# SchematicMasterModulePCB.net
KiCad netlist of a schematic drawn in EAGLE
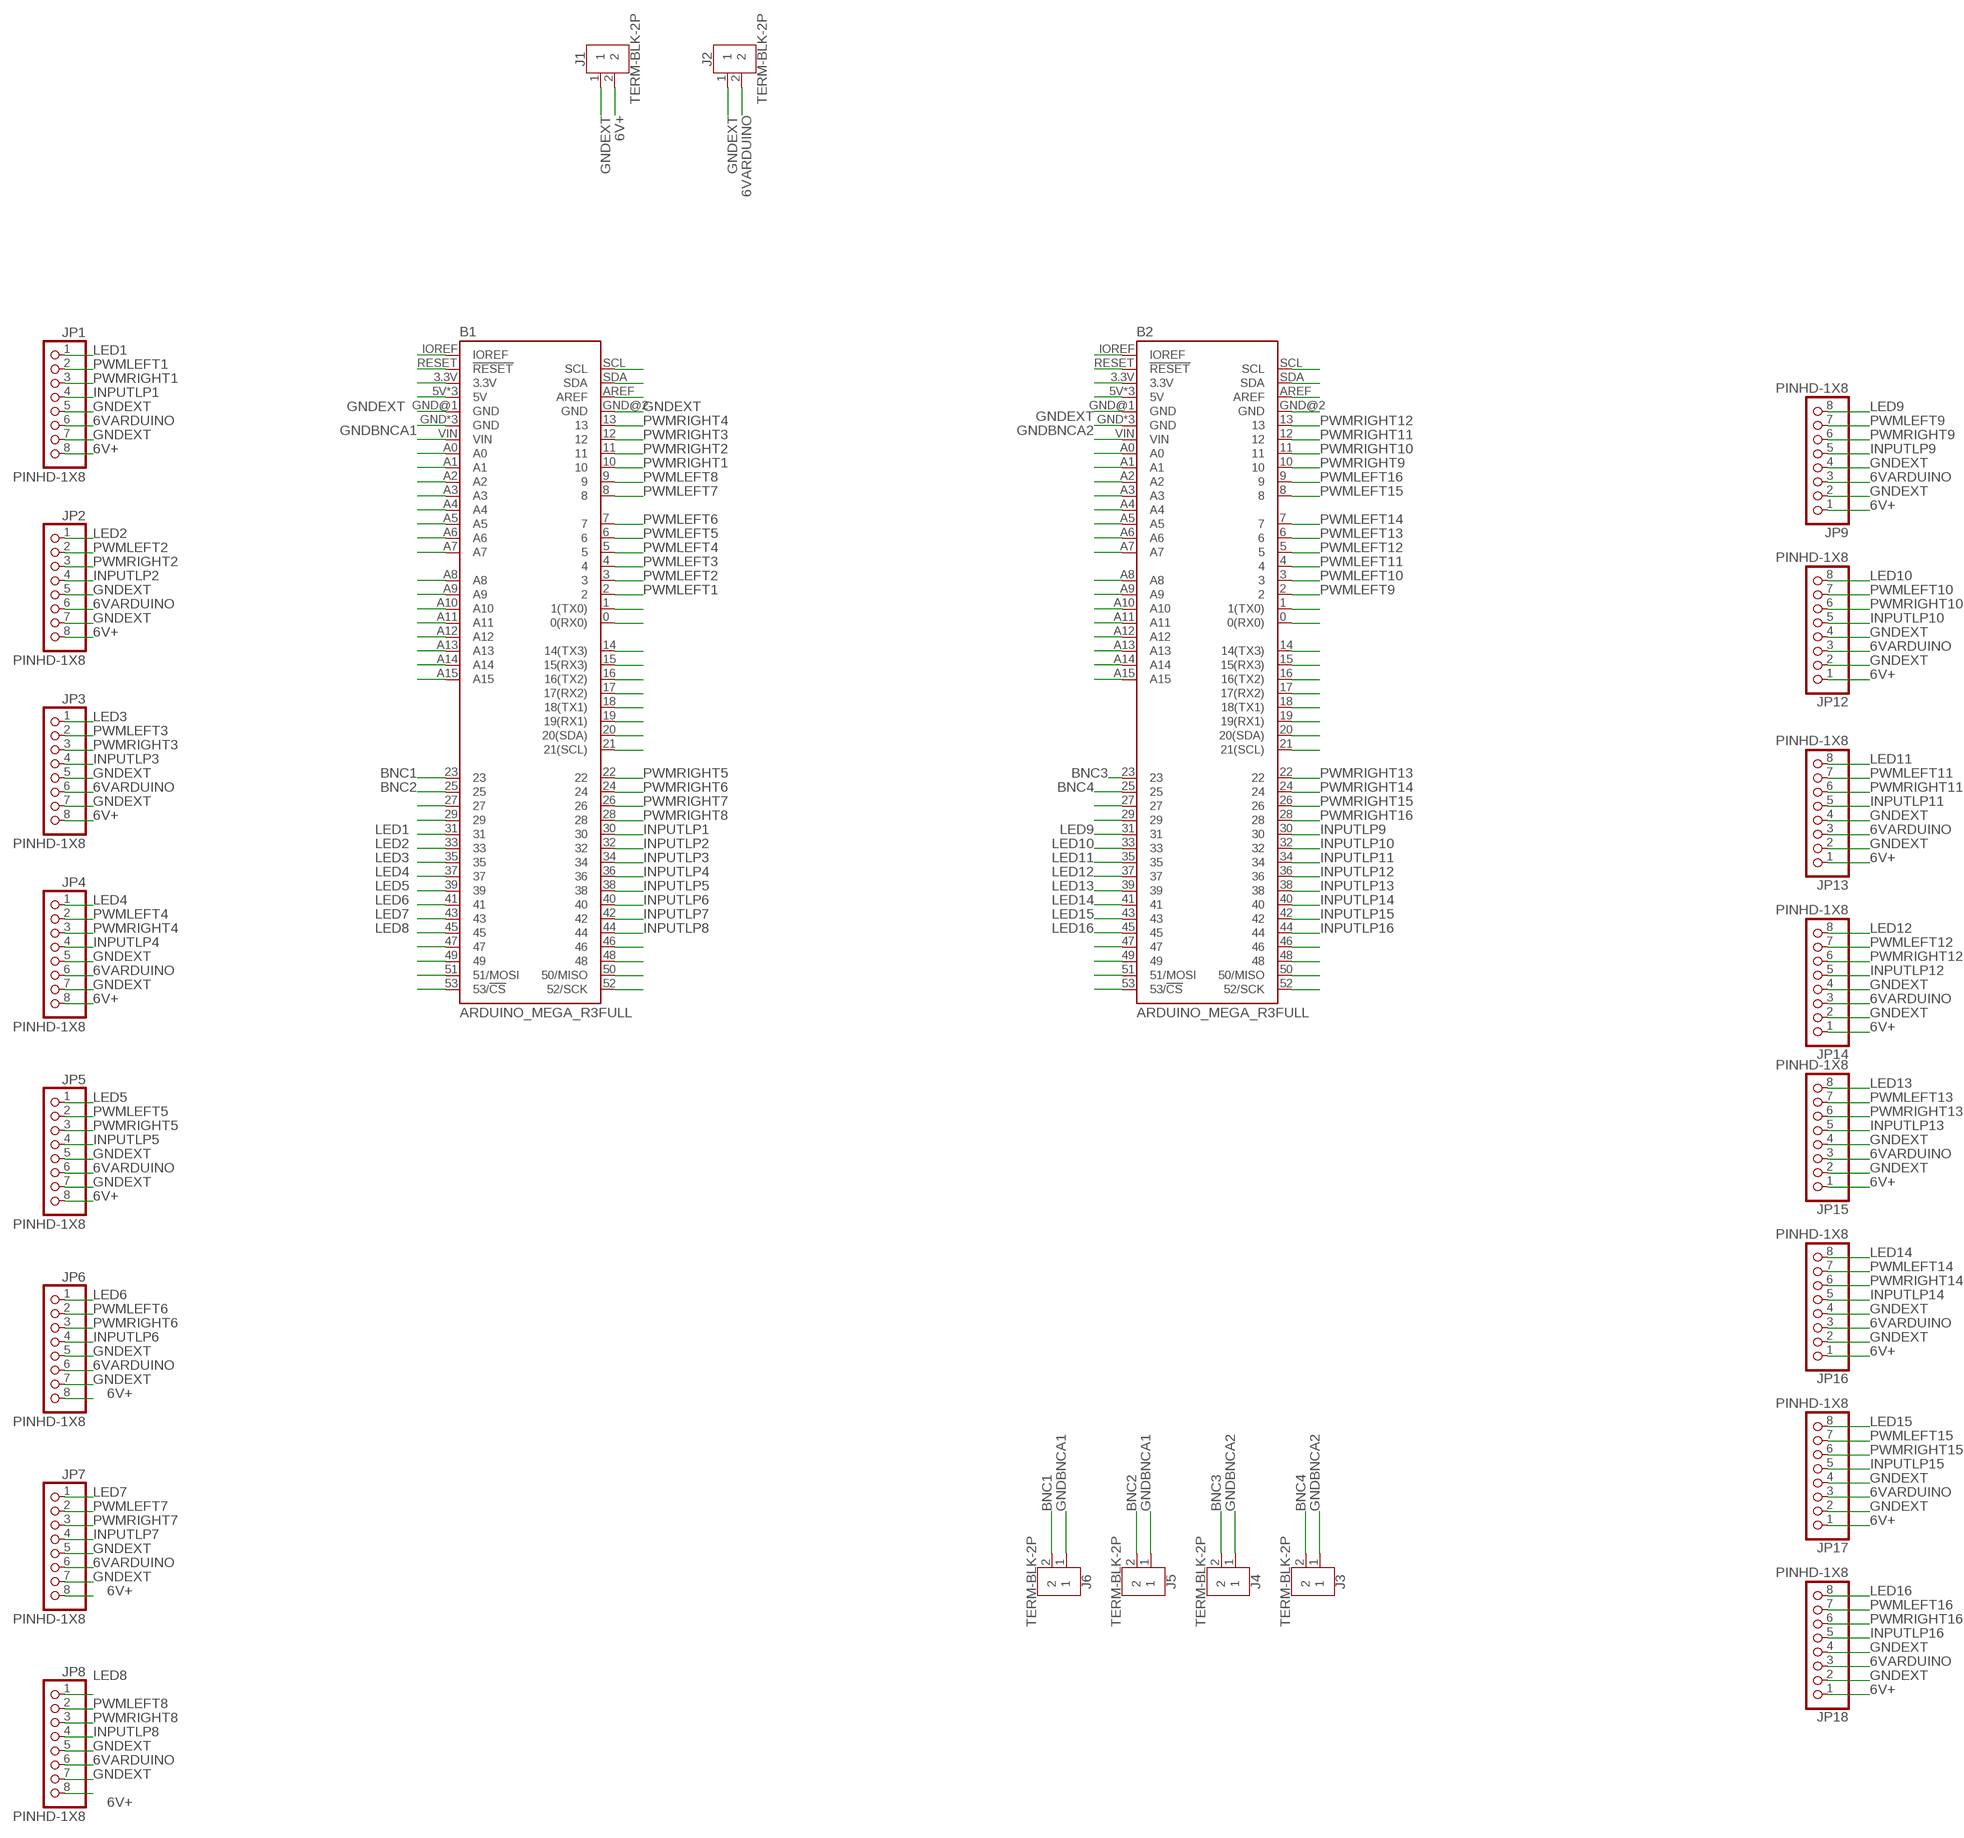
[diagram p0: schematic, sheet 1]

(export (version "E")
  (design (tool "Eeschema 10.0.6"))
  (components
    (comp (ref "B1")
      (value "ARDUINO_MEGA_R3FULL")
      (footprint "eagle-import:ARDUINO_MEGA_NO_SILK")
      (libsource (lib "eagle-import") (part "ARDUINO_MEGA_R3FULL"))
    )
    (comp (ref "B2")
      (value "ARDUINO_MEGA_R3FULL")
      (footprint "eagle-import:ARDUINO_MEGA_NO_SILK")
      (libsource (lib "eagle-import") (part "ARDUINO_MEGA_R3FULL"))
    )
    (comp (ref "J1")
      (value "TERM-BLK-2P")
      (footprint "eagle-import:TERMBLK_508-2N")
      (fields (field (name "MANUFACTURER") "TE Connectivity AMP Connectors") (field (name "MPN") "282837-2"))
      (libsource (lib "eagle-import") (part "2PINSCREWTERMINAL282837-2"))
    )
    (comp (ref "J2")
      (value "TERM-BLK-2P")
      (footprint "eagle-import:TERMBLK_508-2N")
      (fields (field (name "MANUFACTURER") "TE Connectivity AMP Connectors") (field (name "MPN") "282837-2"))
      (libsource (lib "eagle-import") (part "2PINSCREWTERMINAL282837-2"))
    )
    (comp (ref "J3")
      (value "TERM-BLK-2P")
      (footprint "eagle-import:TERMBLK_508-2N")
      (fields (field (name "MANUFACTURER") "TE Connectivity AMP Connectors") (field (name "MPN") "282837-2"))
      (libsource (lib "eagle-import") (part "2PINSCREWTERMINAL282837-2"))
    )
    (comp (ref "J4")
      (value "TERM-BLK-2P")
      (footprint "eagle-import:TERMBLK_508-2N")
      (fields (field (name "MANUFACTURER") "TE Connectivity AMP Connectors") (field (name "MPN") "282837-2"))
      (libsource (lib "eagle-import") (part "2PINSCREWTERMINAL282837-2"))
    )
    (comp (ref "J5")
      (value "TERM-BLK-2P")
      (footprint "eagle-import:TERMBLK_508-2N")
      (fields (field (name "MANUFACTURER") "TE Connectivity AMP Connectors") (field (name "MPN") "282837-2"))
      (libsource (lib "eagle-import") (part "2PINSCREWTERMINAL282837-2"))
    )
    (comp (ref "J6")
      (value "TERM-BLK-2P")
      (footprint "eagle-import:TERMBLK_508-2N")
      (fields (field (name "MANUFACTURER") "TE Connectivity AMP Connectors") (field (name "MPN") "282837-2"))
      (libsource (lib "eagle-import") (part "2PINSCREWTERMINAL282837-2"))
    )
    (comp (ref "JP1")
      (value "PINHD-1X8")
      (footprint "eagle-import:1X08")
      (fields (field (name "MANUFACTURER") "Generic"))
      (libsource (lib "eagle-import") (part "PINHD-1X8"))
    )
    (comp (ref "JP2")
      (value "PINHD-1X8")
      (footprint "eagle-import:1X08")
      (fields (field (name "MANUFACTURER") "Generic"))
      (libsource (lib "eagle-import") (part "PINHD-1X8"))
    )
    (comp (ref "JP3")
      (value "PINHD-1X8")
      (footprint "eagle-import:1X08")
      (fields (field (name "MANUFACTURER") "Generic"))
      (libsource (lib "eagle-import") (part "PINHD-1X8"))
    )
    (comp (ref "JP4")
      (value "PINHD-1X8")
      (footprint "eagle-import:1X08")
      (fields (field (name "MANUFACTURER") "Generic"))
      (libsource (lib "eagle-import") (part "PINHD-1X8"))
    )
    (comp (ref "JP5")
      (value "PINHD-1X8")
      (footprint "eagle-import:1X08")
      (fields (field (name "MANUFACTURER") "Generic"))
      (libsource (lib "eagle-import") (part "PINHD-1X8"))
    )
    (comp (ref "JP6")
      (value "PINHD-1X8")
      (footprint "eagle-import:1X08")
      (fields (field (name "MANUFACTURER") "Generic"))
      (libsource (lib "eagle-import") (part "PINHD-1X8"))
    )
    (comp (ref "JP7")
      (value "PINHD-1X8")
      (footprint "eagle-import:1X08")
      (fields (field (name "MANUFACTURER") "Generic"))
      (libsource (lib "eagle-import") (part "PINHD-1X8"))
    )
    (comp (ref "JP8")
      (value "PINHD-1X8")
      (footprint "eagle-import:1X08")
      (fields (field (name "MANUFACTURER") "Generic"))
      (libsource (lib "eagle-import") (part "PINHD-1X8"))
    )
    (comp (ref "JP9")
      (value "PINHD-1X8")
      (footprint "eagle-import:1X08")
      (fields (field (name "MANUFACTURER") "Generic"))
      (libsource (lib "eagle-import") (part "PINHD-1X8"))
    )
    (comp (ref "JP12")
      (value "PINHD-1X8")
      (footprint "eagle-import:1X08")
      (fields (field (name "MANUFACTURER") "Generic"))
      (libsource (lib "eagle-import") (part "PINHD-1X8"))
    )
    (comp (ref "JP13")
      (value "PINHD-1X8")
      (footprint "eagle-import:1X08")
      (fields (field (name "MANUFACTURER") "Generic"))
      (libsource (lib "eagle-import") (part "PINHD-1X8"))
    )
    (comp (ref "JP14")
      (value "PINHD-1X8")
      (footprint "eagle-import:1X08")
      (fields (field (name "MANUFACTURER") "Generic"))
      (libsource (lib "eagle-import") (part "PINHD-1X8"))
    )
    (comp (ref "JP15")
      (value "PINHD-1X8")
      (footprint "eagle-import:1X08")
      (fields (field (name "MANUFACTURER") "Generic"))
      (libsource (lib "eagle-import") (part "PINHD-1X8"))
    )
    (comp (ref "JP16")
      (value "PINHD-1X8")
      (footprint "eagle-import:1X08")
      (fields (field (name "MANUFACTURER") "Generic"))
      (libsource (lib "eagle-import") (part "PINHD-1X8"))
    )
    (comp (ref "JP17")
      (value "PINHD-1X8")
      (footprint "eagle-import:1X08")
      (fields (field (name "MANUFACTURER") "Generic"))
      (libsource (lib "eagle-import") (part "PINHD-1X8"))
    )
    (comp (ref "JP18")
      (value "PINHD-1X8")
      (footprint "eagle-import:1X08")
      (fields (field (name "MANUFACTURER") "Generic"))
      (libsource (lib "eagle-import") (part "PINHD-1X8"))
    )
  )
  (nets
    (net (code "1") (name "/6V+") (class "Default")
      (node (ref "J1") (pin "2") (pinfunction "2_2") (pintype "bidirectional"))
      (node (ref "JP1") (pin "8") (pinfunction "8_8") (pintype "passive"))
      (node (ref "JP12") (pin "1") (pinfunction "1_1") (pintype "passive"))
      (node (ref "JP13") (pin "1") (pinfunction "1_1") (pintype "passive"))
      (node (ref "JP14") (pin "1") (pinfunction "1_1") (pintype "passive"))
      (node (ref "JP15") (pin "1") (pinfunction "1_1") (pintype "passive"))
      (node (ref "JP16") (pin "1") (pinfunction "1_1") (pintype "passive"))
      (node (ref "JP17") (pin "1") (pinfunction "1_1") (pintype "passive"))
      (node (ref "JP18") (pin "1") (pinfunction "1_1") (pintype "passive"))
      (node (ref "JP2") (pin "8") (pinfunction "8_8") (pintype "passive"))
      (node (ref "JP3") (pin "8") (pinfunction "8_8") (pintype "passive"))
      (node (ref "JP4") (pin "8") (pinfunction "8_8") (pintype "passive"))
      (node (ref "JP5") (pin "8") (pinfunction "8_8") (pintype "passive"))
      (node (ref "JP6") (pin "8") (pinfunction "8_8") (pintype "passive"))
      (node (ref "JP7") (pin "8") (pinfunction "8_8") (pintype "passive"))
      (node (ref "JP8") (pin "8") (pinfunction "8_8") (pintype "passive"))
      (node (ref "JP9") (pin "1") (pinfunction "1_1") (pintype "passive"))
    )
    (net (code "2") (name "/6VARDUINO") (class "Default")
      (node (ref "J2") (pin "2") (pinfunction "2_2") (pintype "bidirectional"))
      (node (ref "JP1") (pin "6") (pinfunction "6_6") (pintype "passive"))
      (node (ref "JP12") (pin "3") (pinfunction "3_3") (pintype "passive"))
      (node (ref "JP13") (pin "3") (pinfunction "3_3") (pintype "passive"))
      (node (ref "JP14") (pin "3") (pinfunction "3_3") (pintype "passive"))
      (node (ref "JP15") (pin "3") (pinfunction "3_3") (pintype "passive"))
      (node (ref "JP16") (pin "3") (pinfunction "3_3") (pintype "passive"))
      (node (ref "JP17") (pin "3") (pinfunction "3_3") (pintype "passive"))
      (node (ref "JP18") (pin "3") (pinfunction "3_3") (pintype "passive"))
      (node (ref "JP2") (pin "6") (pinfunction "6_6") (pintype "passive"))
      (node (ref "JP3") (pin "6") (pinfunction "6_6") (pintype "passive"))
      (node (ref "JP4") (pin "6") (pinfunction "6_6") (pintype "passive"))
      (node (ref "JP5") (pin "6") (pinfunction "6_6") (pintype "passive"))
      (node (ref "JP6") (pin "6") (pinfunction "6_6") (pintype "passive"))
      (node (ref "JP7") (pin "6") (pinfunction "6_6") (pintype "passive"))
      (node (ref "JP8") (pin "6") (pinfunction "6_6") (pintype "passive"))
      (node (ref "JP9") (pin "3") (pinfunction "3_3") (pintype "passive"))
    )
    (net (code "3") (name "/BNC1") (class "Default")
      (node (ref "B1") (pin "23") (pinfunction "23_23") (pintype "bidirectional"))
      (node (ref "J6") (pin "2") (pinfunction "2_2") (pintype "bidirectional"))
    )
    (net (code "4") (name "/BNC2") (class "Default")
      (node (ref "B1") (pin "25") (pinfunction "25_25") (pintype "bidirectional"))
      (node (ref "J5") (pin "2") (pinfunction "2_2") (pintype "bidirectional"))
    )
    (net (code "5") (name "/BNC3") (class "Default")
      (node (ref "B2") (pin "23") (pinfunction "23_23") (pintype "bidirectional"))
      (node (ref "J4") (pin "2") (pinfunction "2_2") (pintype "bidirectional"))
    )
    (net (code "6") (name "/BNC4") (class "Default")
      (node (ref "B2") (pin "25") (pinfunction "25_25") (pintype "bidirectional"))
      (node (ref "J3") (pin "2") (pinfunction "2_2") (pintype "bidirectional"))
    )
    (net (code "7") (name "/GNDBNCA1") (class "Default")
      (node (ref "B1") (pin "GND") (pinfunction "GND_GND") (pintype "bidirectional"))
      (node (ref "B1") (pin "GND@3") (pinfunction "GND_GND@3") (pintype "bidirectional"))
      (node (ref "B1") (pin "GND@4") (pinfunction "GND_GND@4") (pintype "bidirectional"))
      (node (ref "J5") (pin "1") (pinfunction "1_1") (pintype "bidirectional"))
      (node (ref "J6") (pin "1") (pinfunction "1_1") (pintype "bidirectional"))
    )
    (net (code "8") (name "/GNDBNCA2") (class "Default")
      (node (ref "B2") (pin "GND") (pinfunction "GND_GND") (pintype "bidirectional"))
      (node (ref "B2") (pin "GND@3") (pinfunction "GND_GND@3") (pintype "bidirectional"))
      (node (ref "B2") (pin "GND@4") (pinfunction "GND_GND@4") (pintype "bidirectional"))
      (node (ref "J3") (pin "1") (pinfunction "1_1") (pintype "bidirectional"))
      (node (ref "J4") (pin "1") (pinfunction "1_1") (pintype "bidirectional"))
    )
    (net (code "9") (name "/GNDEXT") (class "Default")
      (node (ref "B1") (pin "GND@1") (pinfunction "GND_GND@1") (pintype "bidirectional"))
      (node (ref "B1") (pin "GND@2") (pinfunction "GND_GND@2") (pintype "bidirectional"))
      (node (ref "B2") (pin "GND@1") (pinfunction "GND_GND@1") (pintype "bidirectional"))
      (node (ref "J1") (pin "1") (pinfunction "1_1") (pintype "bidirectional"))
      (node (ref "J2") (pin "1") (pinfunction "1_1") (pintype "bidirectional"))
      (node (ref "JP1") (pin "5") (pinfunction "5_5") (pintype "passive"))
      (node (ref "JP1") (pin "7") (pinfunction "7_7") (pintype "passive"))
      (node (ref "JP12") (pin "2") (pinfunction "2_2") (pintype "passive"))
      (node (ref "JP12") (pin "4") (pinfunction "4_4") (pintype "passive"))
      (node (ref "JP13") (pin "2") (pinfunction "2_2") (pintype "passive"))
      (node (ref "JP13") (pin "4") (pinfunction "4_4") (pintype "passive"))
      (node (ref "JP14") (pin "2") (pinfunction "2_2") (pintype "passive"))
      (node (ref "JP14") (pin "4") (pinfunction "4_4") (pintype "passive"))
      (node (ref "JP15") (pin "2") (pinfunction "2_2") (pintype "passive"))
      (node (ref "JP15") (pin "4") (pinfunction "4_4") (pintype "passive"))
      (node (ref "JP16") (pin "2") (pinfunction "2_2") (pintype "passive"))
      (node (ref "JP16") (pin "4") (pinfunction "4_4") (pintype "passive"))
      (node (ref "JP17") (pin "2") (pinfunction "2_2") (pintype "passive"))
      (node (ref "JP17") (pin "4") (pinfunction "4_4") (pintype "passive"))
      (node (ref "JP18") (pin "2") (pinfunction "2_2") (pintype "passive"))
      (node (ref "JP18") (pin "4") (pinfunction "4_4") (pintype "passive"))
      (node (ref "JP2") (pin "5") (pinfunction "5_5") (pintype "passive"))
      (node (ref "JP2") (pin "7") (pinfunction "7_7") (pintype "passive"))
      (node (ref "JP3") (pin "5") (pinfunction "5_5") (pintype "passive"))
      (node (ref "JP3") (pin "7") (pinfunction "7_7") (pintype "passive"))
      (node (ref "JP4") (pin "5") (pinfunction "5_5") (pintype "passive"))
      (node (ref "JP4") (pin "7") (pinfunction "7_7") (pintype "passive"))
      (node (ref "JP5") (pin "5") (pinfunction "5_5") (pintype "passive"))
      (node (ref "JP5") (pin "7") (pinfunction "7_7") (pintype "passive"))
      (node (ref "JP6") (pin "5") (pinfunction "5_5") (pintype "passive"))
      (node (ref "JP6") (pin "7") (pinfunction "7_7") (pintype "passive"))
      (node (ref "JP7") (pin "5") (pinfunction "5_5") (pintype "passive"))
      (node (ref "JP7") (pin "7") (pinfunction "7_7") (pintype "passive"))
      (node (ref "JP8") (pin "5") (pinfunction "5_5") (pintype "passive"))
      (node (ref "JP8") (pin "7") (pinfunction "7_7") (pintype "passive"))
      (node (ref "JP9") (pin "2") (pinfunction "2_2") (pintype "passive"))
      (node (ref "JP9") (pin "4") (pinfunction "4_4") (pintype "passive"))
    )
    (net (code "10") (name "/INPUTLP1") (class "Default")
      (node (ref "B1") (pin "30") (pinfunction "30_30") (pintype "bidirectional"))
      (node (ref "JP1") (pin "4") (pinfunction "4_4") (pintype "passive"))
    )
    (net (code "11") (name "/INPUTLP2") (class "Default")
      (node (ref "B1") (pin "32") (pinfunction "32_32") (pintype "bidirectional"))
      (node (ref "JP2") (pin "4") (pinfunction "4_4") (pintype "passive"))
    )
    (net (code "12") (name "/INPUTLP3") (class "Default")
      (node (ref "B1") (pin "34") (pinfunction "34_34") (pintype "bidirectional"))
      (node (ref "JP3") (pin "4") (pinfunction "4_4") (pintype "passive"))
    )
    (net (code "13") (name "/INPUTLP4") (class "Default")
      (node (ref "B1") (pin "36") (pinfunction "36_36") (pintype "bidirectional"))
      (node (ref "JP4") (pin "4") (pinfunction "4_4") (pintype "passive"))
    )
    (net (code "14") (name "/INPUTLP5") (class "Default")
      (node (ref "B1") (pin "38") (pinfunction "38_38") (pintype "bidirectional"))
      (node (ref "JP5") (pin "4") (pinfunction "4_4") (pintype "passive"))
    )
    (net (code "15") (name "/INPUTLP6") (class "Default")
      (node (ref "B1") (pin "40") (pinfunction "40_40") (pintype "bidirectional"))
      (node (ref "JP6") (pin "4") (pinfunction "4_4") (pintype "passive"))
    )
    (net (code "16") (name "/INPUTLP7") (class "Default")
      (node (ref "B1") (pin "42") (pinfunction "42_42") (pintype "bidirectional"))
      (node (ref "JP7") (pin "4") (pinfunction "4_4") (pintype "passive"))
    )
    (net (code "17") (name "/INPUTLP8") (class "Default")
      (node (ref "B1") (pin "44") (pinfunction "44_44") (pintype "bidirectional"))
      (node (ref "JP8") (pin "4") (pinfunction "4_4") (pintype "passive"))
    )
    (net (code "18") (name "/INPUTLP9") (class "Default")
      (node (ref "B2") (pin "30") (pinfunction "30_30") (pintype "bidirectional"))
      (node (ref "JP9") (pin "5") (pinfunction "5_5") (pintype "passive"))
    )
    (net (code "19") (name "/INPUTLP10") (class "Default")
      (node (ref "B2") (pin "32") (pinfunction "32_32") (pintype "bidirectional"))
      (node (ref "JP12") (pin "5") (pinfunction "5_5") (pintype "passive"))
    )
    (net (code "20") (name "/INPUTLP11") (class "Default")
      (node (ref "B2") (pin "34") (pinfunction "34_34") (pintype "bidirectional"))
      (node (ref "JP13") (pin "5") (pinfunction "5_5") (pintype "passive"))
    )
    (net (code "21") (name "/INPUTLP12") (class "Default")
      (node (ref "B2") (pin "36") (pinfunction "36_36") (pintype "bidirectional"))
      (node (ref "JP14") (pin "5") (pinfunction "5_5") (pintype "passive"))
    )
    (net (code "22") (name "/INPUTLP13") (class "Default")
      (node (ref "B2") (pin "38") (pinfunction "38_38") (pintype "bidirectional"))
      (node (ref "JP15") (pin "5") (pinfunction "5_5") (pintype "passive"))
    )
    (net (code "23") (name "/INPUTLP14") (class "Default")
      (node (ref "B2") (pin "40") (pinfunction "40_40") (pintype "bidirectional"))
      (node (ref "JP16") (pin "5") (pinfunction "5_5") (pintype "passive"))
    )
    (net (code "24") (name "/INPUTLP15") (class "Default")
      (node (ref "B2") (pin "42") (pinfunction "42_42") (pintype "bidirectional"))
      (node (ref "JP17") (pin "5") (pinfunction "5_5") (pintype "passive"))
    )
    (net (code "25") (name "/INPUTLP16") (class "Default")
      (node (ref "B2") (pin "44") (pinfunction "44_44") (pintype "bidirectional"))
      (node (ref "JP18") (pin "5") (pinfunction "5_5") (pintype "passive"))
    )
    (net (code "26") (name "/LED1") (class "Default")
      (node (ref "B1") (pin "31") (pinfunction "31_31") (pintype "bidirectional"))
      (node (ref "JP1") (pin "1") (pinfunction "1_1") (pintype "passive"))
    )
    (net (code "27") (name "/LED2") (class "Default")
      (node (ref "B1") (pin "33") (pinfunction "33_33") (pintype "bidirectional"))
      (node (ref "JP2") (pin "1") (pinfunction "1_1") (pintype "passive"))
    )
    (net (code "28") (name "/LED3") (class "Default")
      (node (ref "B1") (pin "35") (pinfunction "35_35") (pintype "bidirectional"))
      (node (ref "JP3") (pin "1") (pinfunction "1_1") (pintype "passive"))
    )
    (net (code "29") (name "/LED4") (class "Default")
      (node (ref "B1") (pin "37") (pinfunction "37_37") (pintype "bidirectional"))
      (node (ref "JP4") (pin "1") (pinfunction "1_1") (pintype "passive"))
    )
    (net (code "30") (name "/LED5") (class "Default")
      (node (ref "B1") (pin "39") (pinfunction "39_39") (pintype "bidirectional"))
      (node (ref "JP5") (pin "1") (pinfunction "1_1") (pintype "passive"))
    )
    (net (code "31") (name "/LED6") (class "Default")
      (node (ref "B1") (pin "41") (pinfunction "41_41") (pintype "bidirectional"))
      (node (ref "JP6") (pin "1") (pinfunction "1_1") (pintype "passive"))
    )
    (net (code "32") (name "/LED7") (class "Default")
      (node (ref "B1") (pin "43") (pinfunction "43_43") (pintype "bidirectional"))
      (node (ref "JP7") (pin "1") (pinfunction "1_1") (pintype "passive"))
    )
    (net (code "33") (name "/LED8") (class "Default")
      (node (ref "B1") (pin "45") (pinfunction "45_45") (pintype "bidirectional"))
      (node (ref "JP8") (pin "1") (pinfunction "1_1") (pintype "passive"))
    )
    (net (code "34") (name "/LED9") (class "Default")
      (node (ref "B2") (pin "31") (pinfunction "31_31") (pintype "bidirectional"))
      (node (ref "JP9") (pin "8") (pinfunction "8_8") (pintype "passive"))
    )
    (net (code "35") (name "/LED10") (class "Default")
      (node (ref "B2") (pin "33") (pinfunction "33_33") (pintype "bidirectional"))
      (node (ref "JP12") (pin "8") (pinfunction "8_8") (pintype "passive"))
    )
    (net (code "36") (name "/LED11") (class "Default")
      (node (ref "B2") (pin "35") (pinfunction "35_35") (pintype "bidirectional"))
      (node (ref "JP13") (pin "8") (pinfunction "8_8") (pintype "passive"))
    )
    (net (code "37") (name "/LED12") (class "Default")
      (node (ref "B2") (pin "37") (pinfunction "37_37") (pintype "bidirectional"))
      (node (ref "JP14") (pin "8") (pinfunction "8_8") (pintype "passive"))
    )
    (net (code "38") (name "/LED13") (class "Default")
      (node (ref "B2") (pin "39") (pinfunction "39_39") (pintype "bidirectional"))
      (node (ref "JP15") (pin "8") (pinfunction "8_8") (pintype "passive"))
    )
    (net (code "39") (name "/LED14") (class "Default")
      (node (ref "B2") (pin "41") (pinfunction "41_41") (pintype "bidirectional"))
      (node (ref "JP16") (pin "8") (pinfunction "8_8") (pintype "passive"))
    )
    (net (code "40") (name "/LED15") (class "Default")
      (node (ref "B2") (pin "43") (pinfunction "43_43") (pintype "bidirectional"))
      (node (ref "JP17") (pin "8") (pinfunction "8_8") (pintype "passive"))
    )
    (net (code "41") (name "/LED16") (class "Default")
      (node (ref "B2") (pin "45") (pinfunction "45_45") (pintype "bidirectional"))
      (node (ref "JP18") (pin "8") (pinfunction "8_8") (pintype "passive"))
    )
    (net (code "42") (name "/PWMLEFT1") (class "Default")
      (node (ref "B1") (pin "2") (pinfunction "2_2") (pintype "bidirectional"))
      (node (ref "JP1") (pin "2") (pinfunction "2_2") (pintype "passive"))
    )
    (net (code "43") (name "/PWMLEFT2") (class "Default")
      (node (ref "B1") (pin "3") (pinfunction "3_3") (pintype "bidirectional"))
      (node (ref "JP2") (pin "2") (pinfunction "2_2") (pintype "passive"))
    )
    (net (code "44") (name "/PWMLEFT3") (class "Default")
      (node (ref "B1") (pin "4") (pinfunction "4_4") (pintype "bidirectional"))
      (node (ref "JP3") (pin "2") (pinfunction "2_2") (pintype "passive"))
    )
    (net (code "45") (name "/PWMLEFT4") (class "Default")
      (node (ref "B1") (pin "5") (pinfunction "5_5") (pintype "bidirectional"))
      (node (ref "JP4") (pin "2") (pinfunction "2_2") (pintype "passive"))
    )
    (net (code "46") (name "/PWMLEFT5") (class "Default")
      (node (ref "B1") (pin "6") (pinfunction "6_6") (pintype "bidirectional"))
      (node (ref "JP5") (pin "2") (pinfunction "2_2") (pintype "passive"))
    )
    (net (code "47") (name "/PWMLEFT6") (class "Default")
      (node (ref "B1") (pin "7") (pinfunction "7_7") (pintype "bidirectional"))
      (node (ref "JP6") (pin "2") (pinfunction "2_2") (pintype "passive"))
    )
    (net (code "48") (name "/PWMLEFT7") (class "Default")
      (node (ref "B1") (pin "8") (pinfunction "8_8") (pintype "bidirectional"))
      (node (ref "JP7") (pin "2") (pinfunction "2_2") (pintype "passive"))
    )
    (net (code "49") (name "/PWMLEFT8") (class "Default")
      (node (ref "B1") (pin "9") (pinfunction "9_9") (pintype "bidirectional"))
      (node (ref "JP8") (pin "2") (pinfunction "2_2") (pintype "passive"))
    )
    (net (code "50") (name "/PWMLEFT9") (class "Default")
      (node (ref "B2") (pin "2") (pinfunction "2_2") (pintype "bidirectional"))
      (node (ref "JP9") (pin "7") (pinfunction "7_7") (pintype "passive"))
    )
    (net (code "51") (name "/PWMLEFT10") (class "Default")
      (node (ref "B2") (pin "3") (pinfunction "3_3") (pintype "bidirectional"))
      (node (ref "JP12") (pin "7") (pinfunction "7_7") (pintype "passive"))
    )
    (net (code "52") (name "/PWMLEFT11") (class "Default")
      (node (ref "B2") (pin "4") (pinfunction "4_4") (pintype "bidirectional"))
      (node (ref "JP13") (pin "7") (pinfunction "7_7") (pintype "passive"))
    )
    (net (code "53") (name "/PWMLEFT12") (class "Default")
      (node (ref "B2") (pin "5") (pinfunction "5_5") (pintype "bidirectional"))
      (node (ref "JP14") (pin "7") (pinfunction "7_7") (pintype "passive"))
    )
    (net (code "54") (name "/PWMLEFT13") (class "Default")
      (node (ref "B2") (pin "6") (pinfunction "6_6") (pintype "bidirectional"))
      (node (ref "JP15") (pin "7") (pinfunction "7_7") (pintype "passive"))
    )
    (net (code "55") (name "/PWMLEFT14") (class "Default")
      (node (ref "B2") (pin "7") (pinfunction "7_7") (pintype "bidirectional"))
      (node (ref "JP16") (pin "7") (pinfunction "7_7") (pintype "passive"))
    )
    (net (code "56") (name "/PWMLEFT15") (class "Default")
      (node (ref "B2") (pin "8") (pinfunction "8_8") (pintype "bidirectional"))
      (node (ref "JP17") (pin "7") (pinfunction "7_7") (pintype "passive"))
    )
    (net (code "57") (name "/PWMLEFT16") (class "Default")
      (node (ref "B2") (pin "9") (pinfunction "9_9") (pintype "bidirectional"))
      (node (ref "JP18") (pin "7") (pinfunction "7_7") (pintype "passive"))
    )
    (net (code "58") (name "/PWMRIGHT1") (class "Default")
      (node (ref "B1") (pin "10") (pinfunction "10_10") (pintype "bidirectional"))
      (node (ref "JP1") (pin "3") (pinfunction "3_3") (pintype "passive"))
    )
    (net (code "59") (name "/PWMRIGHT2") (class "Default")
      (node (ref "B1") (pin "11") (pinfunction "11_11") (pintype "bidirectional"))
      (node (ref "JP2") (pin "3") (pinfunction "3_3") (pintype "passive"))
    )
    (net (code "60") (name "/PWMRIGHT3") (class "Default")
      (node (ref "B1") (pin "12") (pinfunction "12_12") (pintype "bidirectional"))
      (node (ref "JP3") (pin "3") (pinfunction "3_3") (pintype "passive"))
    )
    (net (code "61") (name "/PWMRIGHT4") (class "Default")
      (node (ref "B1") (pin "13") (pinfunction "13_13") (pintype "bidirectional"))
      (node (ref "JP4") (pin "3") (pinfunction "3_3") (pintype "passive"))
    )
    (net (code "62") (name "/PWMRIGHT5") (class "Default")
      (node (ref "B1") (pin "22") (pinfunction "22_22") (pintype "bidirectional"))
      (node (ref "JP5") (pin "3") (pinfunction "3_3") (pintype "passive"))
    )
    (net (code "63") (name "/PWMRIGHT6") (class "Default")
      (node (ref "B1") (pin "24") (pinfunction "24_24") (pintype "bidirectional"))
      (node (ref "JP6") (pin "3") (pinfunction "3_3") (pintype "passive"))
    )
    (net (code "64") (name "/PWMRIGHT7") (class "Default")
      (node (ref "B1") (pin "26") (pinfunction "26_26") (pintype "bidirectional"))
      (node (ref "JP7") (pin "3") (pinfunction "3_3") (pintype "passive"))
    )
    (net (code "65") (name "/PWMRIGHT8") (class "Default")
      (node (ref "B1") (pin "28") (pinfunction "28_28") (pintype "bidirectional"))
      (node (ref "JP8") (pin "3") (pinfunction "3_3") (pintype "passive"))
    )
    (net (code "66") (name "/PWMRIGHT9") (class "Default")
      (node (ref "B2") (pin "10") (pinfunction "10_10") (pintype "bidirectional"))
      (node (ref "JP9") (pin "6") (pinfunction "6_6") (pintype "passive"))
    )
    (net (code "67") (name "/PWMRIGHT10") (class "Default")
      (node (ref "B2") (pin "11") (pinfunction "11_11") (pintype "bidirectional"))
      (node (ref "JP12") (pin "6") (pinfunction "6_6") (pintype "passive"))
    )
    (net (code "68") (name "/PWMRIGHT11") (class "Default")
      (node (ref "B2") (pin "12") (pinfunction "12_12") (pintype "bidirectional"))
      (node (ref "JP13") (pin "6") (pinfunction "6_6") (pintype "passive"))
    )
    (net (code "69") (name "/PWMRIGHT12") (class "Default")
      (node (ref "B2") (pin "13") (pinfunction "13_13") (pintype "bidirectional"))
      (node (ref "JP14") (pin "6") (pinfunction "6_6") (pintype "passive"))
    )
    (net (code "70") (name "/PWMRIGHT13") (class "Default")
      (node (ref "B2") (pin "22") (pinfunction "22_22") (pintype "bidirectional"))
      (node (ref "JP15") (pin "6") (pinfunction "6_6") (pintype "passive"))
    )
    (net (code "71") (name "/PWMRIGHT14") (class "Default")
      (node (ref "B2") (pin "24") (pinfunction "24_24") (pintype "bidirectional"))
      (node (ref "JP16") (pin "6") (pinfunction "6_6") (pintype "passive"))
    )
    (net (code "72") (name "/PWMRIGHT15") (class "Default")
      (node (ref "B2") (pin "26") (pinfunction "26_26") (pintype "bidirectional"))
      (node (ref "JP17") (pin "6") (pinfunction "6_6") (pintype "passive"))
    )
    (net (code "73") (name "/PWMRIGHT16") (class "Default")
      (node (ref "B2") (pin "28") (pinfunction "28_28") (pintype "bidirectional"))
      (node (ref "JP18") (pin "6") (pinfunction "6_6") (pintype "passive"))
    )
    (net (code "74") (name "Net-(B1-5V-Pad5V@1)") (class "Default")
      (node (ref "B1") (pin "5V") (pinfunction "5V_5V") (pintype "bidirectional"))
      (node (ref "B1") (pin "5V@1") (pinfunction "5V_5V@1") (pintype "bidirectional"))
      (node (ref "B1") (pin "5V@2") (pinfunction "5V_5V@2") (pintype "bidirectional"))
    )
    (net (code "75") (name "Net-(B2-5V-Pad5V@1)") (class "Default")
      (node (ref "B2") (pin "5V") (pinfunction "5V_5V") (pintype "bidirectional"))
      (node (ref "B2") (pin "5V@1") (pinfunction "5V_5V@1") (pintype "bidirectional"))
      (node (ref "B2") (pin "5V@2") (pinfunction "5V_5V@2") (pintype "bidirectional"))
    )
    (net (code "76") (name "unconnected-(B1-0(RX0)-Pad0)") (class "Default")
      (node (ref "B1") (pin "0") (pinfunction "0(RX0)_0") (pintype "bidirectional"))
    )
    (net (code "77") (name "unconnected-(B1-1(TX0)-Pad1)") (class "Default")
      (node (ref "B1") (pin "1") (pinfunction "1(TX0)_1") (pintype "bidirectional"))
    )
    (net (code "78") (name "unconnected-(B1-14(TX3)-Pad14)") (class "Default")
      (node (ref "B1") (pin "14") (pinfunction "14(TX3)_14") (pintype "bidirectional"))
    )
    (net (code "79") (name "unconnected-(B1-15(RX3)-Pad15)") (class "Default")
      (node (ref "B1") (pin "15") (pinfunction "15(RX3)_15") (pintype "bidirectional"))
    )
    (net (code "80") (name "unconnected-(B1-16(TX2)-Pad16)") (class "Default")
      (node (ref "B1") (pin "16") (pinfunction "16(TX2)_16") (pintype "bidirectional"))
    )
    (net (code "81") (name "unconnected-(B1-17(RX2)-Pad17)") (class "Default")
      (node (ref "B1") (pin "17") (pinfunction "17(RX2)_17") (pintype "bidirectional"))
    )
    (net (code "82") (name "unconnected-(B1-18(TX1)-Pad18)") (class "Default")
      (node (ref "B1") (pin "18") (pinfunction "18(TX1)_18") (pintype "bidirectional"))
    )
    (net (code "83") (name "unconnected-(B1-19(RX1)-Pad19)") (class "Default")
      (node (ref "B1") (pin "19") (pinfunction "19(RX1)_19") (pintype "bidirectional"))
    )
    (net (code "84") (name "unconnected-(B1-20(SDA)-Pad20)") (class "Default")
      (node (ref "B1") (pin "20") (pinfunction "20(SDA)_20") (pintype "bidirectional"))
    )
    (net (code "85") (name "unconnected-(B1-21(SCL)-Pad21)") (class "Default")
      (node (ref "B1") (pin "21") (pinfunction "21(SCL)_21") (pintype "bidirectional"))
    )
    (net (code "86") (name "unconnected-(B1-50{slash}MISO-Pad50)") (class "Default")
      (node (ref "B1") (pin "50") (pinfunction "50/MISO_50") (pintype "bidirectional"))
    )
    (net (code "87") (name "unconnected-(B1-51{slash}MOSI-Pad51)") (class "Default")
      (node (ref "B1") (pin "51") (pinfunction "51/MOSI_51") (pintype "bidirectional"))
    )
    (net (code "88") (name "unconnected-(B1-52{slash}SCK-Pad52)") (class "Default")
      (node (ref "B1") (pin "52") (pinfunction "52/SCK_52") (pintype "bidirectional"))
    )
    (net (code "89") (name "unconnected-(B1-53{slash}~{CS}-Pad53)") (class "Default")
      (node (ref "B1") (pin "53") (pinfunction "53/~{CS}_53") (pintype "bidirectional"))
    )
    (net (code "90") (name "unconnected-(B1-Pad3.3V)") (class "Default")
      (node (ref "B1") (pin "3.3V") (pinfunction "3.3V_3.3V") (pintype "bidirectional"))
    )
    (net (code "91") (name "unconnected-(B1-Pad27)") (class "Default")
      (node (ref "B1") (pin "27") (pinfunction "27_27") (pintype "bidirectional"))
    )
    (net (code "92") (name "unconnected-(B1-Pad29)") (class "Default")
      (node (ref "B1") (pin "29") (pinfunction "29_29") (pintype "bidirectional"))
    )
    (net (code "93") (name "unconnected-(B1-Pad46)") (class "Default")
      (node (ref "B1") (pin "46") (pinfunction "46_46") (pintype "bidirectional"))
    )
    (net (code "94") (name "unconnected-(B1-Pad47)") (class "Default")
      (node (ref "B1") (pin "47") (pinfunction "47_47") (pintype "bidirectional"))
    )
    (net (code "95") (name "unconnected-(B1-Pad48)") (class "Default")
      (node (ref "B1") (pin "48") (pinfunction "48_48") (pintype "bidirectional"))
    )
    (net (code "96") (name "unconnected-(B1-Pad49)") (class "Default")
      (node (ref "B1") (pin "49") (pinfunction "49_49") (pintype "bidirectional"))
    )
    (net (code "97") (name "unconnected-(B1-PadA0)") (class "Default")
      (node (ref "B1") (pin "A0") (pinfunction "A0_A0") (pintype "bidirectional"))
    )
    (net (code "98") (name "unconnected-(B1-PadA1)") (class "Default")
      (node (ref "B1") (pin "A1") (pinfunction "A1_A1") (pintype "bidirectional"))
    )
    (net (code "99") (name "unconnected-(B1-PadA2)") (class "Default")
      (node (ref "B1") (pin "A2") (pinfunction "A2_A2") (pintype "bidirectional"))
    )
    (net (code "100") (name "unconnected-(B1-PadA3)") (class "Default")
      (node (ref "B1") (pin "A3") (pinfunction "A3_A3") (pintype "bidirectional"))
    )
    (net (code "101") (name "unconnected-(B1-PadA4)") (class "Default")
      (node (ref "B1") (pin "A4") (pinfunction "A4_A4") (pintype "bidirectional"))
    )
    (net (code "102") (name "unconnected-(B1-PadA5)") (class "Default")
      (node (ref "B1") (pin "A5") (pinfunction "A5_A5") (pintype "bidirectional"))
    )
    (net (code "103") (name "unconnected-(B1-PadA6)") (class "Default")
      (node (ref "B1") (pin "A6") (pinfunction "A6_A6") (pintype "bidirectional"))
    )
    (net (code "104") (name "unconnected-(B1-PadA7)") (class "Default")
      (node (ref "B1") (pin "A7") (pinfunction "A7_A7") (pintype "bidirectional"))
    )
    (net (code "105") (name "unconnected-(B1-PadA8)") (class "Default")
      (node (ref "B1") (pin "A8") (pinfunction "A8_A8") (pintype "bidirectional"))
    )
    (net (code "106") (name "unconnected-(B1-PadA9)") (class "Default")
      (node (ref "B1") (pin "A9") (pinfunction "A9_A9") (pintype "bidirectional"))
    )
    (net (code "107") (name "unconnected-(B1-PadA10)") (class "Default")
      (node (ref "B1") (pin "A10") (pinfunction "A10_A10") (pintype "bidirectional"))
    )
    (net (code "108") (name "unconnected-(B1-PadA11)") (class "Default")
      (node (ref "B1") (pin "A11") (pinfunction "A11_A11") (pintype "bidirectional"))
    )
    (net (code "109") (name "unconnected-(B1-PadA12)") (class "Default")
      (node (ref "B1") (pin "A12") (pinfunction "A12_A12") (pintype "bidirectional"))
    )
    (net (code "110") (name "unconnected-(B1-PadA13)") (class "Default")
      (node (ref "B1") (pin "A13") (pinfunction "A13_A13") (pintype "bidirectional"))
    )
    (net (code "111") (name "unconnected-(B1-PadA14)") (class "Default")
      (node (ref "B1") (pin "A14") (pinfunction "A14_A14") (pintype "bidirectional"))
    )
    (net (code "112") (name "unconnected-(B1-PadA15)") (class "Default")
      (node (ref "B1") (pin "A15") (pinfunction "A15_A15") (pintype "bidirectional"))
    )
    (net (code "113") (name "unconnected-(B1-PadAREF)") (class "Default")
      (node (ref "B1") (pin "AREF") (pinfunction "AREF_AREF") (pintype "bidirectional"))
    )
    (net (code "114") (name "unconnected-(B1-PadIOREF)") (class "Default")
      (node (ref "B1") (pin "IOREF") (pinfunction "IOREF_IOREF") (pintype "bidirectional"))
    )
    (net (code "115") (name "unconnected-(B1-PadSCL)") (class "Default")
      (node (ref "B1") (pin "SCL") (pinfunction "SCL_SCL") (pintype "bidirectional"))
    )
    (net (code "116") (name "unconnected-(B1-PadSDA)") (class "Default")
      (node (ref "B1") (pin "SDA") (pinfunction "SDA_SDA") (pintype "bidirectional"))
    )
    (net (code "117") (name "unconnected-(B1-PadVIN)") (class "Default")
      (node (ref "B1") (pin "VIN") (pinfunction "VIN_VIN") (pintype "bidirectional"))
    )
    (net (code "118") (name "unconnected-(B1-~{RESET}-PadRESET)") (class "Default")
      (node (ref "B1") (pin "RESET") (pinfunction "~{RESET}_RESET") (pintype "bidirectional"))
    )
    (net (code "119") (name "unconnected-(B2-0(RX0)-Pad0)") (class "Default")
      (node (ref "B2") (pin "0") (pinfunction "0(RX0)_0") (pintype "bidirectional"))
    )
    (net (code "120") (name "unconnected-(B2-1(TX0)-Pad1)") (class "Default")
      (node (ref "B2") (pin "1") (pinfunction "1(TX0)_1") (pintype "bidirectional"))
    )
    (net (code "121") (name "unconnected-(B2-14(TX3)-Pad14)") (class "Default")
      (node (ref "B2") (pin "14") (pinfunction "14(TX3)_14") (pintype "bidirectional"))
    )
    (net (code "122") (name "unconnected-(B2-15(RX3)-Pad15)") (class "Default")
      (node (ref "B2") (pin "15") (pinfunction "15(RX3)_15") (pintype "bidirectional"))
    )
    (net (code "123") (name "unconnected-(B2-16(TX2)-Pad16)") (class "Default")
      (node (ref "B2") (pin "16") (pinfunction "16(TX2)_16") (pintype "bidirectional"))
    )
    (net (code "124") (name "unconnected-(B2-17(RX2)-Pad17)") (class "Default")
      (node (ref "B2") (pin "17") (pinfunction "17(RX2)_17") (pintype "bidirectional"))
    )
    (net (code "125") (name "unconnected-(B2-18(TX1)-Pad18)") (class "Default")
      (node (ref "B2") (pin "18") (pinfunction "18(TX1)_18") (pintype "bidirectional"))
    )
    (net (code "126") (name "unconnected-(B2-19(RX1)-Pad19)") (class "Default")
      (node (ref "B2") (pin "19") (pinfunction "19(RX1)_19") (pintype "bidirectional"))
    )
    (net (code "127") (name "unconnected-(B2-20(SDA)-Pad20)") (class "Default")
      (node (ref "B2") (pin "20") (pinfunction "20(SDA)_20") (pintype "bidirectional"))
    )
    (net (code "128") (name "unconnected-(B2-21(SCL)-Pad21)") (class "Default")
      (node (ref "B2") (pin "21") (pinfunction "21(SCL)_21") (pintype "bidirectional"))
    )
    (net (code "129") (name "unconnected-(B2-50{slash}MISO-Pad50)") (class "Default")
      (node (ref "B2") (pin "50") (pinfunction "50/MISO_50") (pintype "bidirectional"))
    )
    (net (code "130") (name "unconnected-(B2-51{slash}MOSI-Pad51)") (class "Default")
      (node (ref "B2") (pin "51") (pinfunction "51/MOSI_51") (pintype "bidirectional"))
    )
    (net (code "131") (name "unconnected-(B2-52{slash}SCK-Pad52)") (class "Default")
      (node (ref "B2") (pin "52") (pinfunction "52/SCK_52") (pintype "bidirectional"))
    )
    (net (code "132") (name "unconnected-(B2-53{slash}~{CS}-Pad53)") (class "Default")
      (node (ref "B2") (pin "53") (pinfunction "53/~{CS}_53") (pintype "bidirectional"))
    )
    (net (code "133") (name "unconnected-(B2-GND-PadGND@2)") (class "Default")
      (node (ref "B2") (pin "GND@2") (pinfunction "GND_GND@2") (pintype "bidirectional"))
    )
    (net (code "134") (name "unconnected-(B2-Pad3.3V)") (class "Default")
      (node (ref "B2") (pin "3.3V") (pinfunction "3.3V_3.3V") (pintype "bidirectional"))
    )
    (net (code "135") (name "unconnected-(B2-Pad27)") (class "Default")
      (node (ref "B2") (pin "27") (pinfunction "27_27") (pintype "bidirectional"))
    )
    (net (code "136") (name "unconnected-(B2-Pad29)") (class "Default")
      (node (ref "B2") (pin "29") (pinfunction "29_29") (pintype "bidirectional"))
    )
    (net (code "137") (name "unconnected-(B2-Pad46)") (class "Default")
      (node (ref "B2") (pin "46") (pinfunction "46_46") (pintype "bidirectional"))
    )
    (net (code "138") (name "unconnected-(B2-Pad47)") (class "Default")
      (node (ref "B2") (pin "47") (pinfunction "47_47") (pintype "bidirectional"))
    )
    (net (code "139") (name "unconnected-(B2-Pad48)") (class "Default")
      (node (ref "B2") (pin "48") (pinfunction "48_48") (pintype "bidirectional"))
    )
    (net (code "140") (name "unconnected-(B2-Pad49)") (class "Default")
      (node (ref "B2") (pin "49") (pinfunction "49_49") (pintype "bidirectional"))
    )
    (net (code "141") (name "unconnected-(B2-PadA0)") (class "Default")
      (node (ref "B2") (pin "A0") (pinfunction "A0_A0") (pintype "bidirectional"))
    )
    (net (code "142") (name "unconnected-(B2-PadA1)") (class "Default")
      (node (ref "B2") (pin "A1") (pinfunction "A1_A1") (pintype "bidirectional"))
    )
    (net (code "143") (name "unconnected-(B2-PadA2)") (class "Default")
      (node (ref "B2") (pin "A2") (pinfunction "A2_A2") (pintype "bidirectional"))
    )
    (net (code "144") (name "unconnected-(B2-PadA3)") (class "Default")
      (node (ref "B2") (pin "A3") (pinfunction "A3_A3") (pintype "bidirectional"))
    )
    (net (code "145") (name "unconnected-(B2-PadA4)") (class "Default")
      (node (ref "B2") (pin "A4") (pinfunction "A4_A4") (pintype "bidirectional"))
    )
    (net (code "146") (name "unconnected-(B2-PadA5)") (class "Default")
      (node (ref "B2") (pin "A5") (pinfunction "A5_A5") (pintype "bidirectional"))
    )
    (net (code "147") (name "unconnected-(B2-PadA6)") (class "Default")
      (node (ref "B2") (pin "A6") (pinfunction "A6_A6") (pintype "bidirectional"))
    )
    (net (code "148") (name "unconnected-(B2-PadA7)") (class "Default")
      (node (ref "B2") (pin "A7") (pinfunction "A7_A7") (pintype "bidirectional"))
    )
    (net (code "149") (name "unconnected-(B2-PadA8)") (class "Default")
      (node (ref "B2") (pin "A8") (pinfunction "A8_A8") (pintype "bidirectional"))
    )
    (net (code "150") (name "unconnected-(B2-PadA9)") (class "Default")
      (node (ref "B2") (pin "A9") (pinfunction "A9_A9") (pintype "bidirectional"))
    )
    (net (code "151") (name "unconnected-(B2-PadA10)") (class "Default")
      (node (ref "B2") (pin "A10") (pinfunction "A10_A10") (pintype "bidirectional"))
    )
    (net (code "152") (name "unconnected-(B2-PadA11)") (class "Default")
      (node (ref "B2") (pin "A11") (pinfunction "A11_A11") (pintype "bidirectional"))
    )
    (net (code "153") (name "unconnected-(B2-PadA12)") (class "Default")
      (node (ref "B2") (pin "A12") (pinfunction "A12_A12") (pintype "bidirectional"))
    )
    (net (code "154") (name "unconnected-(B2-PadA13)") (class "Default")
      (node (ref "B2") (pin "A13") (pinfunction "A13_A13") (pintype "bidirectional"))
    )
    (net (code "155") (name "unconnected-(B2-PadA14)") (class "Default")
      (node (ref "B2") (pin "A14") (pinfunction "A14_A14") (pintype "bidirectional"))
    )
    (net (code "156") (name "unconnected-(B2-PadA15)") (class "Default")
      (node (ref "B2") (pin "A15") (pinfunction "A15_A15") (pintype "bidirectional"))
    )
    (net (code "157") (name "unconnected-(B2-PadAREF)") (class "Default")
      (node (ref "B2") (pin "AREF") (pinfunction "AREF_AREF") (pintype "bidirectional"))
    )
    (net (code "158") (name "unconnected-(B2-PadIOREF)") (class "Default")
      (node (ref "B2") (pin "IOREF") (pinfunction "IOREF_IOREF") (pintype "bidirectional"))
    )
    (net (code "159") (name "unconnected-(B2-PadSCL)") (class "Default")
      (node (ref "B2") (pin "SCL") (pinfunction "SCL_SCL") (pintype "bidirectional"))
    )
    (net (code "160") (name "unconnected-(B2-PadSDA)") (class "Default")
      (node (ref "B2") (pin "SDA") (pinfunction "SDA_SDA") (pintype "bidirectional"))
    )
    (net (code "161") (name "unconnected-(B2-PadVIN)") (class "Default")
      (node (ref "B2") (pin "VIN") (pinfunction "VIN_VIN") (pintype "bidirectional"))
    )
    (net (code "162") (name "unconnected-(B2-~{RESET}-PadRESET)") (class "Default")
      (node (ref "B2") (pin "RESET") (pinfunction "~{RESET}_RESET") (pintype "bidirectional"))
    )
  )
)
